# preamp.net
KiCad netlist of a schematic drawn in EAGLE
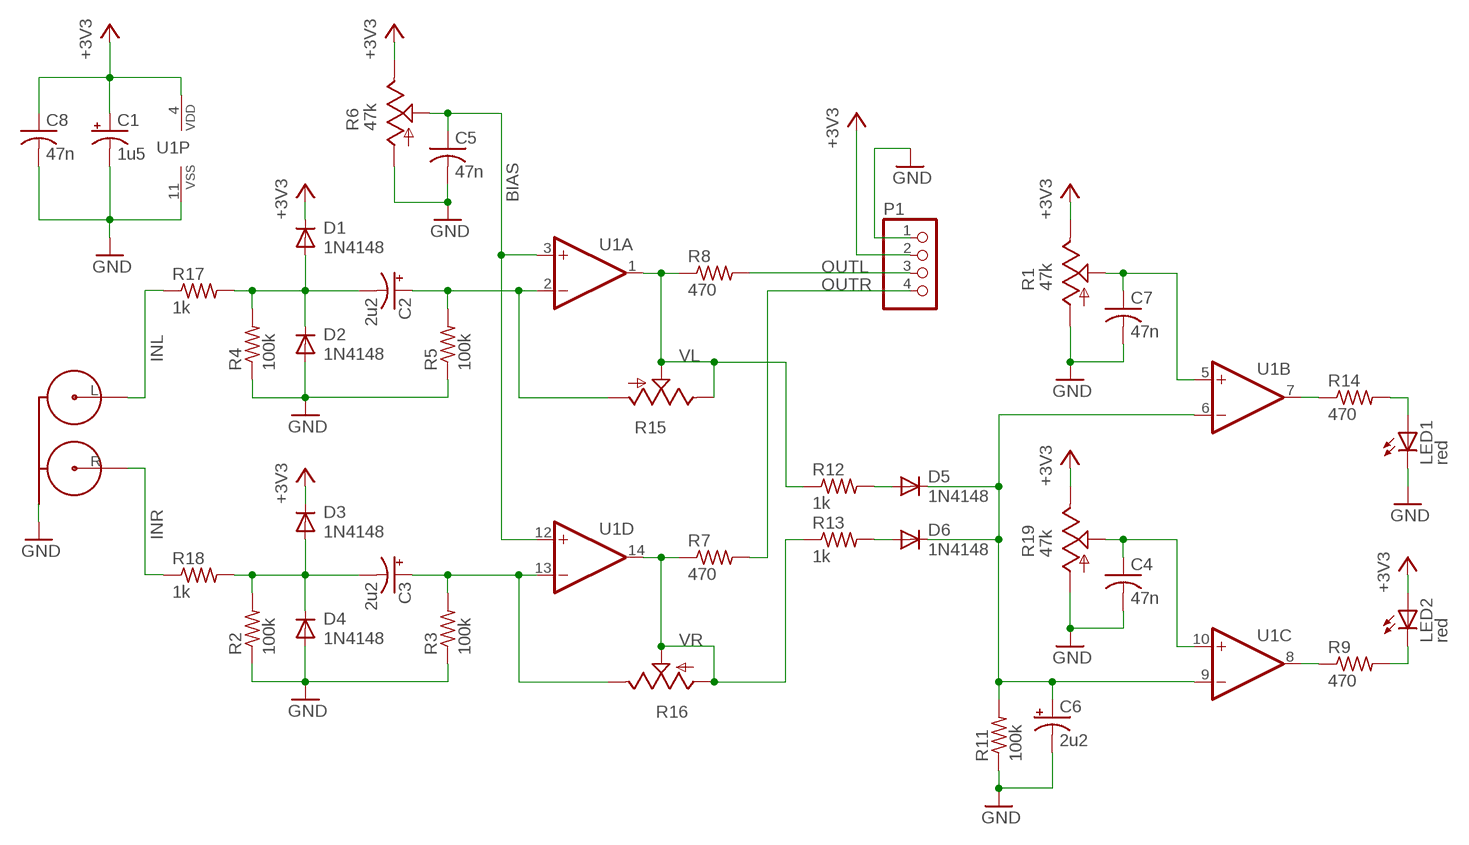
[diagram p0: schematic, sheet 1]

(export (version "E")
  (design (tool "Eeschema 10.0.6"))
  (components
    (comp (ref "C1")
      (value "1u5")
      (footprint "eagle-import:E2-4")
      (libsource (lib "eagle-import") (part "CPOL-USE2-4"))
    )
    (comp (ref "C2")
      (value "2u2")
      (footprint "eagle-import:E2,5-5")
      (libsource (lib "eagle-import") (part "CPOL-USE2.5-5"))
    )
    (comp (ref "C3")
      (value "2u2")
      (footprint "eagle-import:E2,5-5")
      (libsource (lib "eagle-import") (part "CPOL-USE2.5-5"))
    )
    (comp (ref "C4")
      (value "47n")
      (footprint "eagle-import:C050-025X075")
      (libsource (lib "eagle-import") (part "C-US050-025X075"))
    )
    (comp (ref "C5")
      (value "47n")
      (footprint "eagle-import:C050-025X075")
      (libsource (lib "eagle-import") (part "C-US050-025X075"))
    )
    (comp (ref "C6")
      (value "2u2")
      (footprint "eagle-import:E2,5-6")
      (libsource (lib "eagle-import") (part "CPOL-USE2.5-6"))
    )
    (comp (ref "C7")
      (value "47n")
      (footprint "eagle-import:C050-025X075")
      (libsource (lib "eagle-import") (part "C-US050-025X075"))
    )
    (comp (ref "C8")
      (value "47n")
      (footprint "eagle-import:C050-025X075")
      (libsource (lib "eagle-import") (part "C-US050-025X075"))
    )
    (comp (ref "D1")
      (value "1N4148")
      (footprint "eagle-import:DO35-5")
      (libsource (lib "eagle-import") (part "1N4148"))
    )
    (comp (ref "D2")
      (value "1N4148")
      (footprint "eagle-import:DO35-5")
      (libsource (lib "eagle-import") (part "1N4148"))
    )
    (comp (ref "D3")
      (value "1N4148")
      (footprint "eagle-import:DO35-5")
      (libsource (lib "eagle-import") (part "1N4148"))
    )
    (comp (ref "D4")
      (value "1N4148")
      (footprint "eagle-import:DO35-5")
      (libsource (lib "eagle-import") (part "1N4148"))
    )
    (comp (ref "D5")
      (value "1N4148")
      (footprint "eagle-import:DO35-5")
      (libsource (lib "eagle-import") (part "1N4148"))
    )
    (comp (ref "D6")
      (value "1N4148")
      (footprint "eagle-import:DO35-5")
      (libsource (lib "eagle-import") (part "1N4148"))
    )
    (comp (ref "LED1")
      (value "red")
      (footprint "eagle-import:LED3MM")
      (libsource (lib "eagle-import") (part "LED3MM"))
    )
    (comp (ref "LED2")
      (value "red")
      (footprint "eagle-import:LED3MM")
      (libsource (lib "eagle-import") (part "LED3MM"))
    )
    (comp (ref "P1")
      (value "PINHD-1X4")
      (footprint "eagle-import:1X04")
      (libsource (lib "eagle-import") (part "PINHD-1X4"))
    )
    (comp (ref "R1")
      (value "47k")
      (footprint "eagle-import:PT-10S")
      (libsource (lib "eagle-import") (part "TRIM_US-PT-10S"))
    )
    (comp (ref "R2")
      (value "100k")
      (footprint "eagle-import:0204_5")
      (libsource (lib "eagle-import") (part "R-US_0204/5"))
    )
    (comp (ref "R3")
      (value "100k")
      (footprint "eagle-import:0204_5")
      (libsource (lib "eagle-import") (part "R-US_0204/5"))
    )
    (comp (ref "R4")
      (value "100k")
      (footprint "eagle-import:0204_5")
      (libsource (lib "eagle-import") (part "R-US_0204/5"))
    )
    (comp (ref "R5")
      (value "100k")
      (footprint "eagle-import:0204_5")
      (libsource (lib "eagle-import") (part "R-US_0204/5"))
    )
    (comp (ref "R6")
      (value "47k")
      (footprint "eagle-import:PT-10S")
      (libsource (lib "eagle-import") (part "TRIM_US-PT-10S"))
    )
    (comp (ref "R7")
      (value "470")
      (footprint "eagle-import:0204_5")
      (libsource (lib "eagle-import") (part "R-US_0204/5"))
    )
    (comp (ref "R8")
      (value "470")
      (footprint "eagle-import:0204_5")
      (libsource (lib "eagle-import") (part "R-US_0204/5"))
    )
    (comp (ref "R9")
      (value "470")
      (footprint "eagle-import:0204_5")
      (libsource (lib "eagle-import") (part "R-US_0204/5"))
    )
    (comp (ref "R11")
      (value "100k")
      (footprint "eagle-import:0204_5")
      (libsource (lib "eagle-import") (part "R-US_0204/5"))
    )
    (comp (ref "R12")
      (value "1k")
      (footprint "eagle-import:0204_5")
      (libsource (lib "eagle-import") (part "R-US_0204/5"))
    )
    (comp (ref "R13")
      (value "1k")
      (footprint "eagle-import:0204_5")
      (libsource (lib "eagle-import") (part "R-US_0204/5"))
    )
    (comp (ref "R14")
      (value "470")
      (footprint "eagle-import:0204_5")
      (libsource (lib "eagle-import") (part "R-US_0204/5"))
    )
    (comp (ref "R15")
      (value "TRIM_US-S63S")
      (footprint "eagle-import:S63S")
      (libsource (lib "eagle-import") (part "TRIM_US-S63S"))
    )
    (comp (ref "R16")
      (value "TRIM_US-S63S")
      (footprint "eagle-import:S63S")
      (libsource (lib "eagle-import") (part "TRIM_US-S63S"))
    )
    (comp (ref "R17")
      (value "1k")
      (footprint "eagle-import:0204_5")
      (libsource (lib "eagle-import") (part "R-US_0204/5"))
    )
    (comp (ref "R18")
      (value "1k")
      (footprint "eagle-import:0204_5")
      (libsource (lib "eagle-import") (part "R-US_0204/5"))
    )
    (comp (ref "R19")
      (value "47k")
      (footprint "eagle-import:PT-10S")
      (libsource (lib "eagle-import") (part "TRIM_US-PT-10S"))
    )
    (comp (ref "RCA1")
      (value "RCA-2V")
      (footprint "eagle-import:RCA-2V")
      (libsource (lib "eagle-import") (part "RCA-2V"))
    )
    (comp (ref "U1")
      (value "MCP6024-I/P")
      (footprint "eagle-import:DIL14")
      (libsource (lib "eagle-import") (part "MCP6024-I/P"))
    )
  )
  (nets
    (net (code "1") (name "+3V3") (class "Default")
      (node (ref "C1") (pin "+") (pinfunction "+_+") (pintype "passive"))
      (node (ref "C8") (pin "1") (pinfunction "1_1") (pintype "passive"))
      (node (ref "D1") (pin "C") (pinfunction "C_C") (pintype "passive"))
      (node (ref "D3") (pin "C") (pinfunction "C_C") (pintype "passive"))
      (node (ref "LED2") (pin "A") (pinfunction "A_A") (pintype "passive"))
      (node (ref "P1") (pin "2") (pinfunction "2_2") (pintype "passive"))
      (node (ref "R1") (pin "E") (pinfunction "E_E") (pintype "passive"))
      (node (ref "R19") (pin "E") (pinfunction "E_E") (pintype "passive"))
      (node (ref "R6") (pin "E") (pinfunction "E_E") (pintype "passive"))
      (node (ref "U1") (pin "4") (pinfunction "VDD_4") (pintype "passive"))
    )
    (net (code "2") (name "/BIAS") (class "Default")
      (node (ref "C5") (pin "1") (pinfunction "1_1") (pintype "passive"))
      (node (ref "R6") (pin "S") (pinfunction "S_S") (pintype "passive"))
      (node (ref "U1") (pin "12") (pinfunction "+IN_12") (pintype "input"))
      (node (ref "U1") (pin "3") (pinfunction "+IN_3") (pintype "input"))
    )
    (net (code "3") (name "/INL") (class "Default")
      (node (ref "R17") (pin "1") (pinfunction "1_1") (pintype "passive"))
      (node (ref "RCA1") (pin "L") (pinfunction "L_L") (pintype "passive"))
    )
    (net (code "4") (name "/INR") (class "Default")
      (node (ref "R18") (pin "1") (pinfunction "1_1") (pintype "passive"))
      (node (ref "RCA1") (pin "R") (pinfunction "R_R") (pintype "passive"))
    )
    (net (code "5") (name "/OUTL") (class "Default")
      (node (ref "P1") (pin "3") (pinfunction "3_3") (pintype "passive"))
      (node (ref "R8") (pin "2") (pinfunction "2_2") (pintype "passive"))
    )
    (net (code "6") (name "/OUTR") (class "Default")
      (node (ref "P1") (pin "4") (pinfunction "4_4") (pintype "passive"))
      (node (ref "R7") (pin "2") (pinfunction "2_2") (pintype "passive"))
    )
    (net (code "7") (name "/VL") (class "Default")
      (node (ref "R12") (pin "1") (pinfunction "1_1") (pintype "passive"))
      (node (ref "R15") (pin "E") (pinfunction "E_E") (pintype "passive"))
      (node (ref "R15") (pin "S") (pinfunction "S_S") (pintype "passive"))
      (node (ref "R8") (pin "1") (pinfunction "1_1") (pintype "passive"))
      (node (ref "U1") (pin "1") (pinfunction "OUT_1") (pintype "output"))
    )
    (net (code "8") (name "/VR") (class "Default")
      (node (ref "R13") (pin "1") (pinfunction "1_1") (pintype "passive"))
      (node (ref "R16") (pin "A") (pinfunction "A_A") (pintype "passive"))
      (node (ref "R16") (pin "S") (pinfunction "S_S") (pintype "passive"))
      (node (ref "R7") (pin "1") (pinfunction "1_1") (pintype "passive"))
      (node (ref "U1") (pin "14") (pinfunction "OUT_14") (pintype "output"))
    )
    (net (code "9") (name "GND") (class "Default")
      (node (ref "C1") (pin "-") (pinfunction "-_-") (pintype "passive"))
      (node (ref "C4") (pin "2") (pinfunction "2_2") (pintype "passive"))
      (node (ref "C5") (pin "2") (pinfunction "2_2") (pintype "passive"))
      (node (ref "C6") (pin "-") (pinfunction "-_-") (pintype "passive"))
      (node (ref "C7") (pin "2") (pinfunction "2_2") (pintype "passive"))
      (node (ref "C8") (pin "2") (pinfunction "2_2") (pintype "passive"))
      (node (ref "D2") (pin "A") (pinfunction "A_A") (pintype "passive"))
      (node (ref "D4") (pin "A") (pinfunction "A_A") (pintype "passive"))
      (node (ref "LED1") (pin "K") (pinfunction "C_K") (pintype "passive"))
      (node (ref "P1") (pin "1") (pinfunction "1_1") (pintype "passive"))
      (node (ref "R1") (pin "A") (pinfunction "A_A") (pintype "passive"))
      (node (ref "R11") (pin "1") (pinfunction "1_1") (pintype "passive"))
      (node (ref "R19") (pin "A") (pinfunction "A_A") (pintype "passive"))
      (node (ref "R2") (pin "1") (pinfunction "1_1") (pintype "passive"))
      (node (ref "R3") (pin "1") (pinfunction "1_1") (pintype "passive"))
      (node (ref "R4") (pin "1") (pinfunction "1_1") (pintype "passive"))
      (node (ref "R5") (pin "1") (pinfunction "1_1") (pintype "passive"))
      (node (ref "R6") (pin "A") (pinfunction "A_A") (pintype "passive"))
      (node (ref "RCA1") (pin "SHIELD") (pinfunction "SHIELD_SHIELD") (pintype "passive"))
      (node (ref "U1") (pin "11") (pinfunction "VSS_11") (pintype "passive"))
    )
    (net (code "10") (name "Net-(C2-Pad-)") (class "Default")
      (node (ref "C2") (pin "-") (pinfunction "-_-") (pintype "passive"))
      (node (ref "D1") (pin "A") (pinfunction "A_A") (pintype "passive"))
      (node (ref "D2") (pin "C") (pinfunction "C_C") (pintype "passive"))
      (node (ref "R17") (pin "2") (pinfunction "2_2") (pintype "passive"))
      (node (ref "R4") (pin "2") (pinfunction "2_2") (pintype "passive"))
    )
    (net (code "11") (name "Net-(C3-Pad-)") (class "Default")
      (node (ref "C3") (pin "-") (pinfunction "-_-") (pintype "passive"))
      (node (ref "D3") (pin "A") (pinfunction "A_A") (pintype "passive"))
      (node (ref "D4") (pin "C") (pinfunction "C_C") (pintype "passive"))
      (node (ref "R18") (pin "2") (pinfunction "2_2") (pintype "passive"))
      (node (ref "R2") (pin "2") (pinfunction "2_2") (pintype "passive"))
    )
    (net (code "12") (name "Net-(D5-PadA)") (class "Default")
      (node (ref "D5") (pin "A") (pinfunction "A_A") (pintype "passive"))
      (node (ref "R12") (pin "2") (pinfunction "2_2") (pintype "passive"))
    )
    (net (code "13") (name "Net-(D6-PadA)") (class "Default")
      (node (ref "D6") (pin "A") (pinfunction "A_A") (pintype "passive"))
      (node (ref "R13") (pin "2") (pinfunction "2_2") (pintype "passive"))
    )
    (net (code "14") (name "Net-(LED1-PadA)") (class "Default")
      (node (ref "LED1") (pin "A") (pinfunction "A_A") (pintype "passive"))
      (node (ref "R14") (pin "2") (pinfunction "2_2") (pintype "passive"))
    )
    (net (code "15") (name "Net-(LED2-C)") (class "Default")
      (node (ref "LED2") (pin "K") (pinfunction "C_K") (pintype "passive"))
      (node (ref "R9") (pin "2") (pinfunction "2_2") (pintype "passive"))
    )
    (net (code "16") (name "Net-(U1A--IN)") (class "Default")
      (node (ref "C2") (pin "+") (pinfunction "+_+") (pintype "passive"))
      (node (ref "R15") (pin "A") (pinfunction "A_A") (pintype "passive"))
      (node (ref "R5") (pin "2") (pinfunction "2_2") (pintype "passive"))
      (node (ref "U1") (pin "2") (pinfunction "-IN_2") (pintype "input"))
    )
    (net (code "17") (name "Net-(U1B-+IN)") (class "Default")
      (node (ref "C7") (pin "1") (pinfunction "1_1") (pintype "passive"))
      (node (ref "R1") (pin "S") (pinfunction "S_S") (pintype "passive"))
      (node (ref "U1") (pin "5") (pinfunction "+IN_5") (pintype "input"))
    )
    (net (code "18") (name "Net-(U1B--IN)") (class "Default")
      (node (ref "C6") (pin "+") (pinfunction "+_+") (pintype "passive"))
      (node (ref "D5") (pin "C") (pinfunction "C_C") (pintype "passive"))
      (node (ref "D6") (pin "C") (pinfunction "C_C") (pintype "passive"))
      (node (ref "R11") (pin "2") (pinfunction "2_2") (pintype "passive"))
      (node (ref "U1") (pin "6") (pinfunction "-IN_6") (pintype "input"))
      (node (ref "U1") (pin "9") (pinfunction "-IN_9") (pintype "input"))
    )
    (net (code "19") (name "Net-(U1B-OUT)") (class "Default")
      (node (ref "R14") (pin "1") (pinfunction "1_1") (pintype "passive"))
      (node (ref "U1") (pin "7") (pinfunction "OUT_7") (pintype "output"))
    )
    (net (code "20") (name "Net-(U1C-+IN)") (class "Default")
      (node (ref "C4") (pin "1") (pinfunction "1_1") (pintype "passive"))
      (node (ref "R19") (pin "S") (pinfunction "S_S") (pintype "passive"))
      (node (ref "U1") (pin "10") (pinfunction "+IN_10") (pintype "input"))
    )
    (net (code "21") (name "Net-(U1C-OUT)") (class "Default")
      (node (ref "R9") (pin "1") (pinfunction "1_1") (pintype "passive"))
      (node (ref "U1") (pin "8") (pinfunction "OUT_8") (pintype "output"))
    )
    (net (code "22") (name "Net-(U1D--IN)") (class "Default")
      (node (ref "C3") (pin "+") (pinfunction "+_+") (pintype "passive"))
      (node (ref "R16") (pin "E") (pinfunction "E_E") (pintype "passive"))
      (node (ref "R3") (pin "2") (pinfunction "2_2") (pintype "passive"))
      (node (ref "U1") (pin "13") (pinfunction "-IN_13") (pintype "input"))
    )
  )
)
